# alu_slice.net
KiCad netlist of a schematic drawn in EAGLE
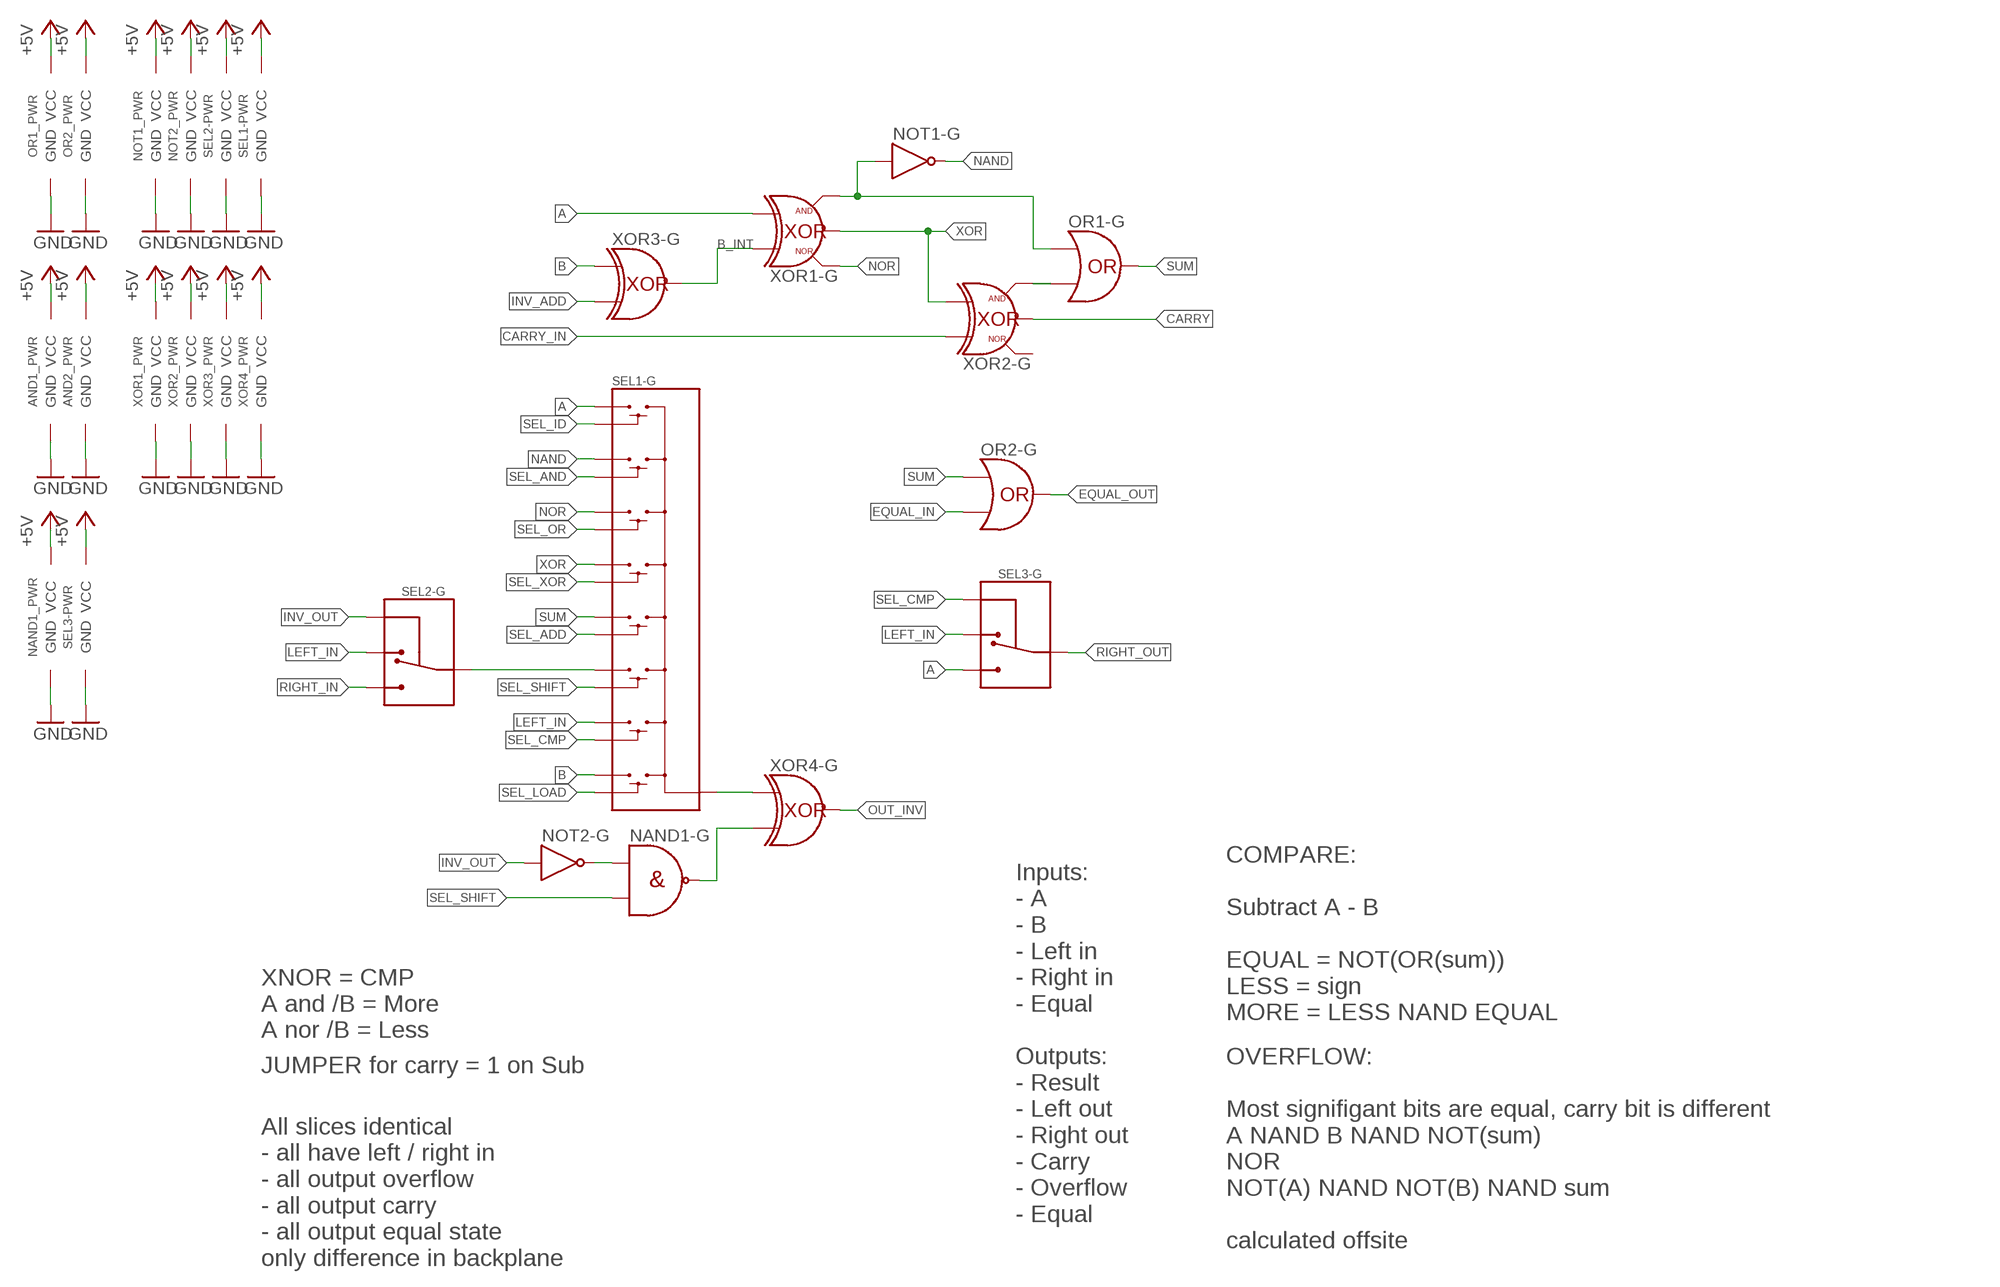
[diagram p0: schematic, sheet 1]

(export (version "E")
  (design (tool "Eeschema 10.0.6"))
  (components
    (comp (ref "AND1")
      (value "AND-UNBUF")
      (footprint "eagle-import:AND-2-UNBUF")
      (libsource (lib "eagle-import") (part "AND-UNBUF"))
    )
    (comp (ref "AND2")
      (value "AND-UNBUF")
      (footprint "eagle-import:AND-2-UNBUF")
      (libsource (lib "eagle-import") (part "AND-UNBUF"))
    )
    (comp (ref "NAND1")
      (value "NAND")
      (footprint "eagle-import:NAND-2")
      (libsource (lib "eagle-import") (part "NAND"))
    )
    (comp (ref "NOT1")
      (value "NOT-VERTICAL")
      (footprint "eagle-import:NOT-VERTICAL")
      (libsource (lib "eagle-import") (part "NOT-VERTICAL"))
    )
    (comp (ref "NOT2")
      (value "NOT-VERTICAL")
      (footprint "eagle-import:NOT-VERTICAL")
      (libsource (lib "eagle-import") (part "NOT-VERTICAL"))
    )
    (comp (ref "OR1")
      (value "OR")
      (footprint "eagle-import:OR-2")
      (libsource (lib "eagle-import") (part "OR"))
    )
    (comp (ref "OR2")
      (value "OR")
      (footprint "eagle-import:OR-2")
      (libsource (lib "eagle-import") (part "OR"))
    )
    (comp (ref "SEL1")
      (value "SELECTOR")
      (footprint "eagle-import:SELECTOR-8_BIT-NOMUX")
      (libsource (lib "eagle-import") (part "SELECTOR"))
    )
    (comp (ref "SEL2")
      (value "SELECTOR-2_LANES")
      (footprint "eagle-import:SELECTOR-2-LANE-NOMUX")
      (libsource (lib "eagle-import") (part "SELECTOR-2_LANES"))
    )
    (comp (ref "SEL3")
      (value "SELECTOR-2_LANES")
      (footprint "eagle-import:SELECTOR-2-LANE-NOMUX")
      (libsource (lib "eagle-import") (part "SELECTOR-2_LANES"))
    )
    (comp (ref "XOR1")
      (value "EX-XOR")
      (footprint "eagle-import:XOR-2-EX2")
      (libsource (lib "eagle-import") (part "EX-XOR"))
    )
    (comp (ref "XOR2")
      (value "EX-XOR")
      (footprint "eagle-import:XOR-2-EX2")
      (libsource (lib "eagle-import") (part "EX-XOR"))
    )
    (comp (ref "XOR3")
      (value "XOR")
      (footprint "eagle-import:XOR-2-EX2")
      (libsource (lib "eagle-import") (part "XOR"))
    )
    (comp (ref "XOR4")
      (value "XOR")
      (footprint "eagle-import:XOR-2-EX2")
      (libsource (lib "eagle-import") (part "XOR"))
    )
  )
  (nets
    (net (code "1") (name "+5V") (class "Default")
      (node (ref "AND1") (pin "OUT3") (pinfunction "VCC_OUT3") (pintype "bidirectional"))
      (node (ref "AND2") (pin "OUT3") (pinfunction "VCC_OUT3") (pintype "bidirectional"))
      (node (ref "NAND1") (pin "OUT1") (pinfunction "VCC_OUT1") (pintype "bidirectional"))
      (node (ref "NOT1") (pin "OUT3") (pinfunction "VCC_OUT3") (pintype "bidirectional"))
      (node (ref "NOT2") (pin "OUT3") (pinfunction "VCC_OUT3") (pintype "bidirectional"))
      (node (ref "OR1") (pin "OUT3") (pinfunction "VCC_OUT3") (pintype "bidirectional"))
      (node (ref "OR2") (pin "OUT3") (pinfunction "VCC_OUT3") (pintype "bidirectional"))
      (node (ref "SEL1") (pin "V+") (pinfunction "VCC_V+") (pintype "bidirectional"))
      (node (ref "SEL2") (pin "V+") (pinfunction "VCC_V+") (pintype "bidirectional"))
      (node (ref "SEL3") (pin "V+") (pinfunction "VCC_V+") (pintype "bidirectional"))
      (node (ref "XOR1") (pin "OUT1") (pinfunction "VCC_OUT1") (pintype "bidirectional"))
      (node (ref "XOR2") (pin "OUT1") (pinfunction "VCC_OUT1") (pintype "bidirectional"))
      (node (ref "XOR3") (pin "OUT1") (pinfunction "VCC_OUT1") (pintype "bidirectional"))
      (node (ref "XOR4") (pin "OUT1") (pinfunction "VCC_OUT1") (pintype "bidirectional"))
    )
    (net (code "2") (name "/B_INT") (class "Default")
      (node (ref "XOR1") (pin "A") (pinfunction "A_A") (pintype "bidirectional"))
      (node (ref "XOR3") (pin "OUT4") (pinfunction "OUT_OUT4") (pintype "bidirectional"))
    )
    (net (code "3") (name "A") (class "Default")
      (node (ref "SEL1") (pin "IN1") (pinfunction "IN1_IN1") (pintype "bidirectional"))
      (node (ref "SEL3") (pin "IN2") (pinfunction "IN2_IN2") (pintype "bidirectional"))
      (node (ref "XOR1") (pin "B") (pinfunction "B_B") (pintype "bidirectional"))
    )
    (net (code "4") (name "B") (class "Default")
      (node (ref "SEL1") (pin "IN8") (pinfunction "IN8_IN8") (pintype "bidirectional"))
      (node (ref "XOR3") (pin "A") (pinfunction "A_A") (pintype "bidirectional"))
    )
    (net (code "5") (name "CARRY") (class "Default")
      (node (ref "XOR2") (pin "OUT4") (pinfunction "OUT_OUT4") (pintype "bidirectional"))
    )
    (net (code "6") (name "CARRY_IN") (class "Default")
      (node (ref "XOR2") (pin "A") (pinfunction "A_A") (pintype "bidirectional"))
    )
    (net (code "7") (name "EQUAL_IN") (class "Default")
      (node (ref "OR2") (pin "B") (pinfunction "B_B") (pintype "bidirectional"))
    )
    (net (code "8") (name "EQUAL_OUT") (class "Default")
      (node (ref "OR2") (pin "OUT1") (pinfunction "OUT_OUT1") (pintype "bidirectional"))
    )
    (net (code "9") (name "GND") (class "Default")
      (node (ref "AND1") (pin "OUT1") (pinfunction "GND_OUT1") (pintype "bidirectional"))
      (node (ref "AND2") (pin "OUT1") (pinfunction "GND_OUT1") (pintype "bidirectional"))
      (node (ref "NAND1") (pin "OUT3") (pinfunction "GND_OUT3") (pintype "bidirectional"))
      (node (ref "NOT1") (pin "OUT2") (pinfunction "GND_OUT2") (pintype "bidirectional"))
      (node (ref "NOT2") (pin "OUT2") (pinfunction "GND_OUT2") (pintype "bidirectional"))
      (node (ref "OR1") (pin "OUT2") (pinfunction "GND_OUT2") (pintype "bidirectional"))
      (node (ref "OR2") (pin "OUT2") (pinfunction "GND_OUT2") (pintype "bidirectional"))
      (node (ref "SEL1") (pin "GND") (pinfunction "GND_GND") (pintype "bidirectional"))
      (node (ref "SEL2") (pin "GND") (pinfunction "GND_GND") (pintype "bidirectional"))
      (node (ref "SEL3") (pin "GND") (pinfunction "GND_GND") (pintype "bidirectional"))
      (node (ref "XOR1") (pin "OUT5") (pinfunction "GND_OUT5") (pintype "bidirectional"))
      (node (ref "XOR2") (pin "OUT5") (pinfunction "GND_OUT5") (pintype "bidirectional"))
      (node (ref "XOR3") (pin "OUT5") (pinfunction "GND_OUT5") (pintype "bidirectional"))
      (node (ref "XOR4") (pin "OUT5") (pinfunction "GND_OUT5") (pintype "bidirectional"))
    )
    (net (code "10") (name "INV_ADD") (class "Default")
      (node (ref "XOR3") (pin "B") (pinfunction "B_B") (pintype "bidirectional"))
    )
    (net (code "11") (name "INV_OUT") (class "Default")
      (node (ref "NOT2") (pin "IN") (pinfunction "IN_IN") (pintype "bidirectional"))
      (node (ref "SEL2") (pin "SEL") (pinfunction "SEL_SEL") (pintype "bidirectional"))
    )
    (net (code "12") (name "LEFT_IN") (class "Default")
      (node (ref "SEL1") (pin "IN7") (pinfunction "IN7_IN7") (pintype "bidirectional"))
      (node (ref "SEL2") (pin "IN1") (pinfunction "IN1_IN1") (pintype "bidirectional"))
      (node (ref "SEL3") (pin "IN1") (pinfunction "IN1_IN1") (pintype "bidirectional"))
    )
    (net (code "13") (name "NAND") (class "Default")
      (node (ref "NOT1") (pin "OUT1") (pinfunction "OUT_OUT1") (pintype "bidirectional"))
      (node (ref "SEL1") (pin "IN2") (pinfunction "IN2_IN2") (pintype "bidirectional"))
    )
    (net (code "14") (name "NOR") (class "Default")
      (node (ref "SEL1") (pin "IN3") (pinfunction "IN3_IN3") (pintype "bidirectional"))
      (node (ref "XOR1") (pin "OUT3") (pinfunction "NOR_OUT3") (pintype "bidirectional"))
    )
    (net (code "15") (name "Net-(NAND1A-A)") (class "Default")
      (node (ref "NAND1") (pin "B") (pinfunction "A_B") (pintype "bidirectional"))
      (node (ref "NOT2") (pin "OUT1") (pinfunction "OUT_OUT1") (pintype "bidirectional"))
    )
    (net (code "16") (name "Net-(NAND1A-OUT)") (class "Default")
      (node (ref "NAND1") (pin "OUT2") (pinfunction "OUT_OUT2") (pintype "bidirectional"))
      (node (ref "XOR4") (pin "B") (pinfunction "B_B") (pintype "bidirectional"))
    )
    (net (code "17") (name "Net-(SEL1-PadIN6)") (class "Default")
      (node (ref "SEL1") (pin "IN6") (pinfunction "IN6_IN6") (pintype "bidirectional"))
      (node (ref "SEL2") (pin "OUT") (pinfunction "OUT_OUT") (pintype "bidirectional"))
    )
    (net (code "18") (name "Net-(SEL1-PadOUT)") (class "Default")
      (node (ref "SEL1") (pin "OUT") (pinfunction "OUT_OUT") (pintype "bidirectional"))
      (node (ref "XOR4") (pin "A") (pinfunction "A_A") (pintype "bidirectional"))
    )
    (net (code "19") (name "Net-(XOR1A-AND)") (class "Default")
      (node (ref "NOT1") (pin "IN") (pinfunction "IN_IN") (pintype "bidirectional"))
      (node (ref "OR1") (pin "A") (pinfunction "A_A") (pintype "bidirectional"))
      (node (ref "XOR1") (pin "OUT2") (pinfunction "AND_OUT2") (pintype "bidirectional"))
    )
    (net (code "20") (name "Net-(XOR2A-AND)") (class "Default")
      (node (ref "OR1") (pin "B") (pinfunction "B_B") (pintype "bidirectional"))
      (node (ref "XOR2") (pin "OUT2") (pinfunction "AND_OUT2") (pintype "bidirectional"))
    )
    (net (code "21") (name "OUT_INV") (class "Default")
      (node (ref "XOR4") (pin "OUT4") (pinfunction "OUT_OUT4") (pintype "bidirectional"))
    )
    (net (code "22") (name "RIGHT_IN") (class "Default")
      (node (ref "SEL2") (pin "IN2") (pinfunction "IN2_IN2") (pintype "bidirectional"))
    )
    (net (code "23") (name "RIGHT_OUT") (class "Default")
      (node (ref "SEL3") (pin "OUT") (pinfunction "OUT_OUT") (pintype "bidirectional"))
    )
    (net (code "24") (name "SEL_ADD") (class "Default")
      (node (ref "SEL1") (pin "SEL5") (pinfunction "SEL5_SEL5") (pintype "bidirectional"))
    )
    (net (code "25") (name "SEL_AND") (class "Default")
      (node (ref "SEL1") (pin "SEL2") (pinfunction "SEL2_SEL2") (pintype "bidirectional"))
    )
    (net (code "26") (name "SEL_CMP") (class "Default")
      (node (ref "SEL1") (pin "SEL7") (pinfunction "SEL7_SEL7") (pintype "bidirectional"))
      (node (ref "SEL3") (pin "SEL") (pinfunction "SEL_SEL") (pintype "bidirectional"))
    )
    (net (code "27") (name "SEL_ID") (class "Default")
      (node (ref "SEL1") (pin "SEL1") (pinfunction "SEL1_SEL1") (pintype "bidirectional"))
    )
    (net (code "28") (name "SEL_LOAD") (class "Default")
      (node (ref "SEL1") (pin "SEL8") (pinfunction "SEL8_SEL8") (pintype "bidirectional"))
    )
    (net (code "29") (name "SEL_OR") (class "Default")
      (node (ref "SEL1") (pin "SEL3") (pinfunction "SEL3_SEL3") (pintype "bidirectional"))
    )
    (net (code "30") (name "SEL_SHIFT") (class "Default")
      (node (ref "NAND1") (pin "A") (pinfunction "B_A") (pintype "bidirectional"))
      (node (ref "SEL1") (pin "SEL6") (pinfunction "SEL6_SEL6") (pintype "bidirectional"))
    )
    (net (code "31") (name "SEL_XOR") (class "Default")
      (node (ref "SEL1") (pin "SEL4") (pinfunction "SEL4_SEL4") (pintype "bidirectional"))
    )
    (net (code "32") (name "SUM") (class "Default")
      (node (ref "OR1") (pin "OUT1") (pinfunction "OUT_OUT1") (pintype "bidirectional"))
      (node (ref "OR2") (pin "A") (pinfunction "A_A") (pintype "bidirectional"))
      (node (ref "SEL1") (pin "IN5") (pinfunction "IN5_IN5") (pintype "bidirectional"))
    )
    (net (code "33") (name "XOR") (class "Default")
      (node (ref "SEL1") (pin "IN4") (pinfunction "IN4_IN4") (pintype "bidirectional"))
      (node (ref "XOR1") (pin "OUT4") (pinfunction "OUT_OUT4") (pintype "bidirectional"))
      (node (ref "XOR2") (pin "B") (pinfunction "B_B") (pintype "bidirectional"))
    )
    (net (code "34") (name "unconnected-(XOR2A-NOR-PadOUT3)") (class "Default")
      (node (ref "XOR2") (pin "OUT3") (pinfunction "NOR_OUT3") (pintype "bidirectional"))
    )
  )
)
